# A5000_8MB_MEMCs.net
KiCad netlist of a schematic drawn in Altium Designer
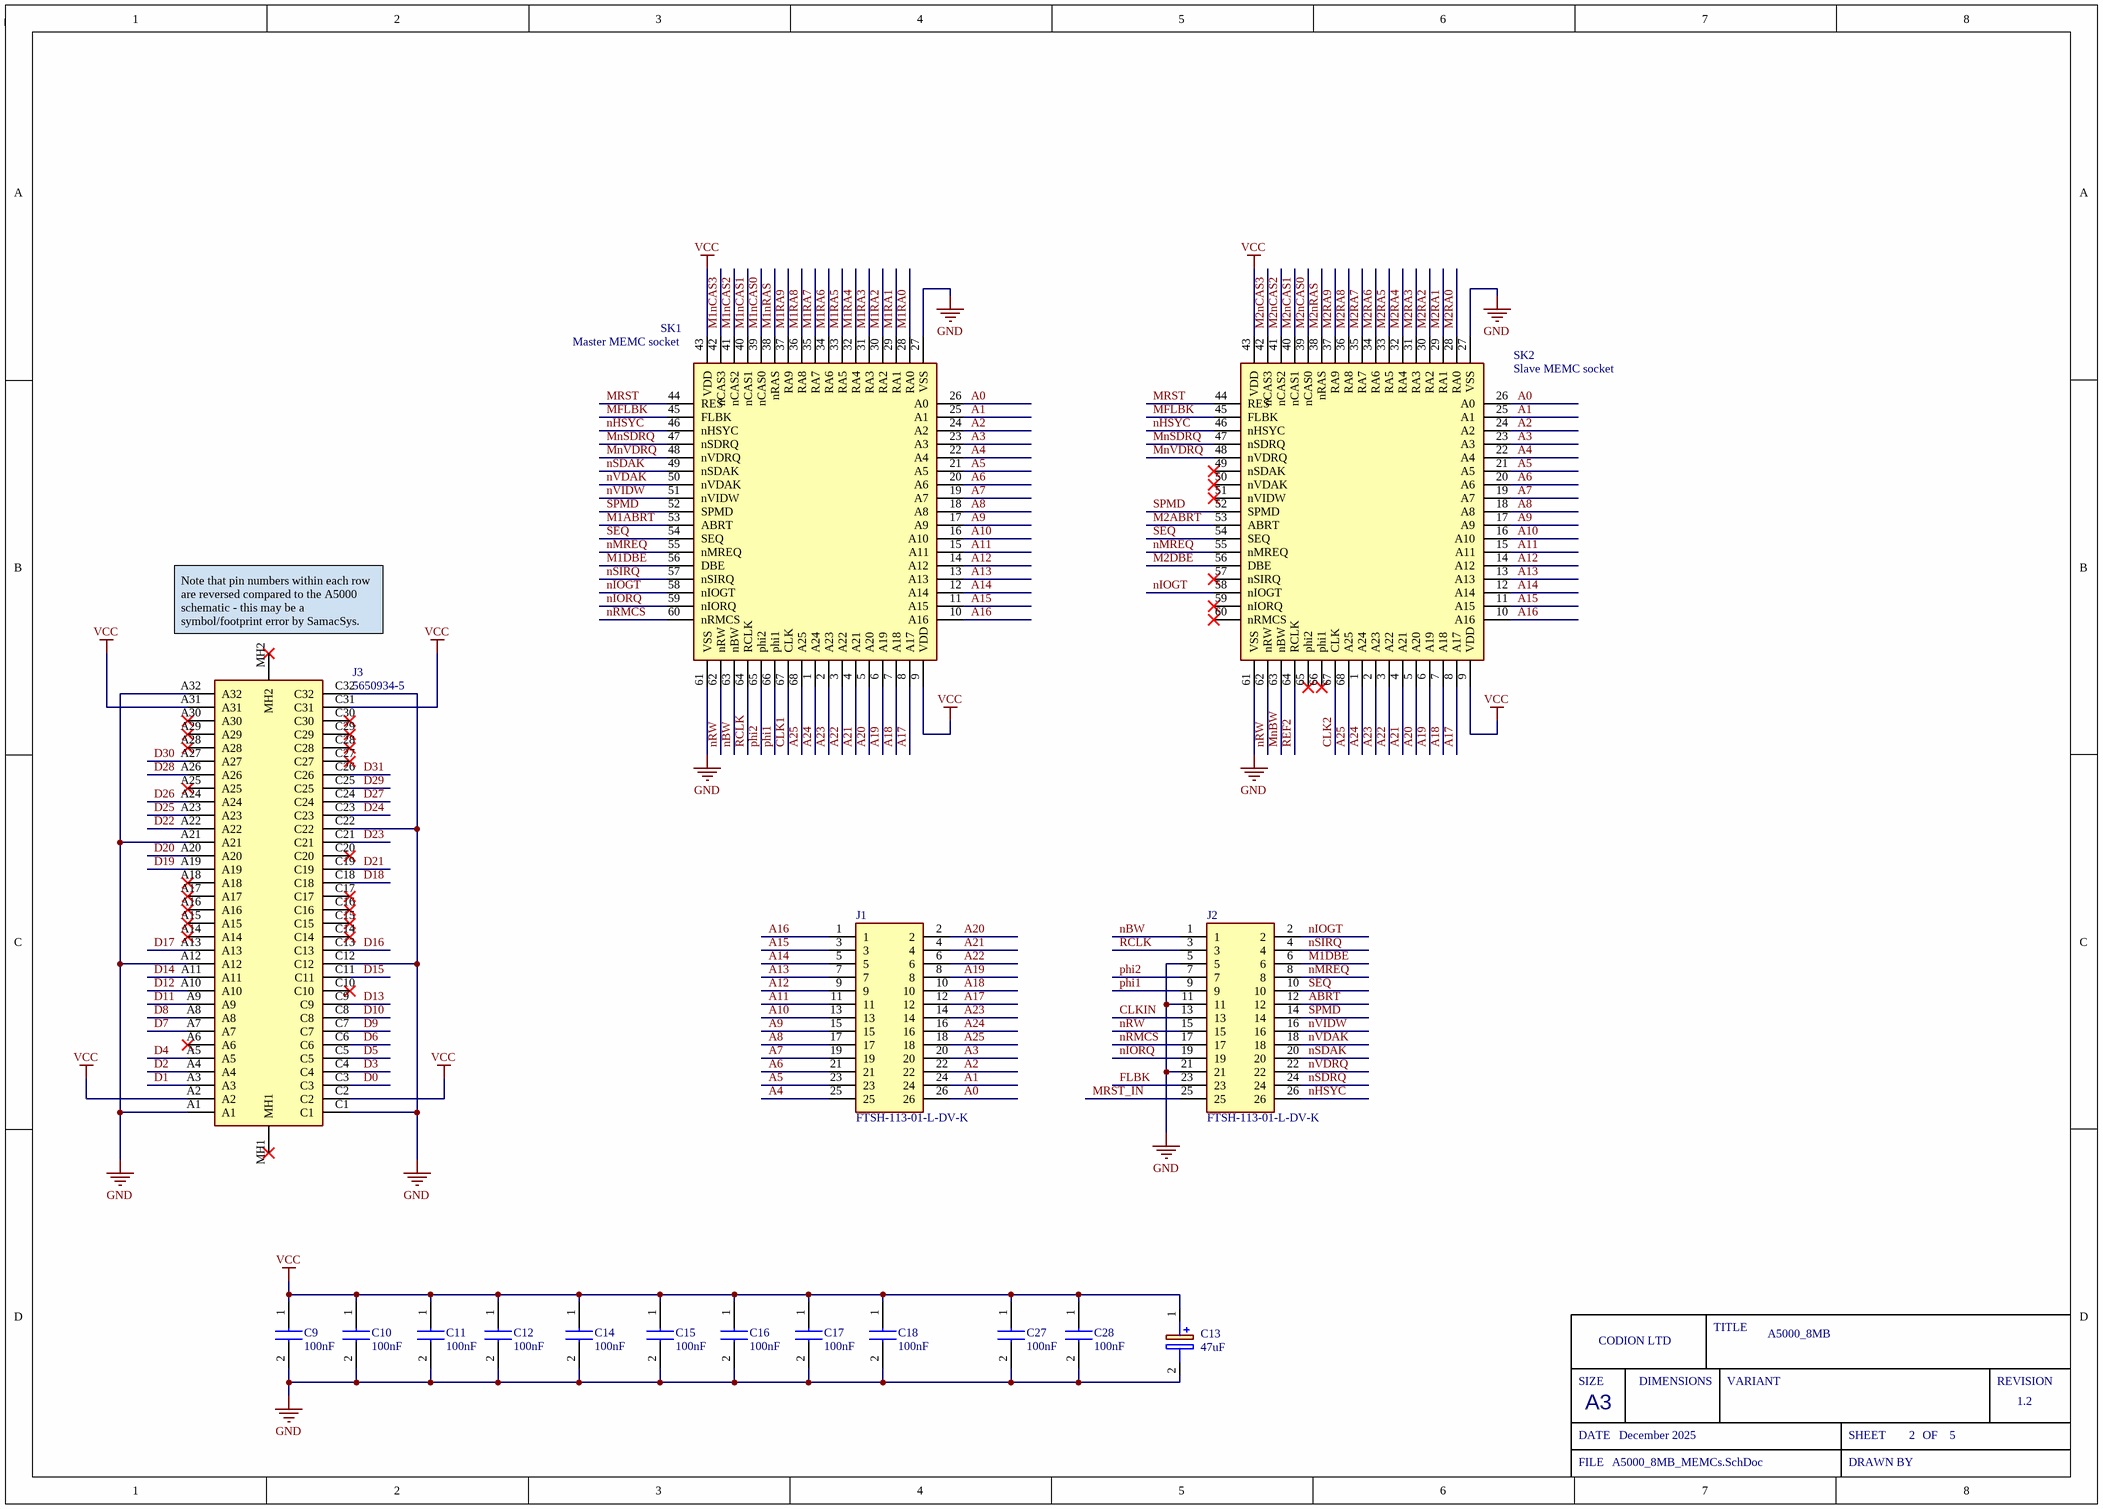
[diagram p0: A5000_8MB_MEMCs.SchDoc]

(export (version "E")
  (design (tool "Eeschema 10.0.6"))
  (components
    (comp (ref "C9")
      (value "100nF")
      (footprint "0805cap")
      (description "Capacitor")
      (fields
        (field (name "MANUFACTURER_PART_NUMBER") "C2012X7R1H104K125AM")
        (field (name "MOUSER PART NUMBER") "810-C2012X7R1H104KT5")
      )
      (libsource (lib "Acorn") (part "100nF0805"))
    )
    (comp (ref "C10")
      (value "100nF")
      (footprint "0805cap")
      (description "Capacitor")
      (fields
        (field (name "MANUFACTURER_PART_NUMBER") "C2012X7R1H104K125AM")
        (field (name "MOUSER PART NUMBER") "810-C2012X7R1H104KT5")
      )
      (libsource (lib "Acorn") (part "100nF0805"))
    )
    (comp (ref "C11")
      (value "100nF")
      (footprint "0805cap")
      (description "Capacitor")
      (fields
        (field (name "MANUFACTURER_PART_NUMBER") "C2012X7R1H104K125AM")
        (field (name "MOUSER PART NUMBER") "810-C2012X7R1H104KT5")
      )
      (libsource (lib "Acorn") (part "100nF0805"))
    )
    (comp (ref "C12")
      (value "100nF")
      (footprint "0805cap")
      (description "Capacitor")
      (fields
        (field (name "MANUFACTURER_PART_NUMBER") "C2012X7R1H104K125AM")
        (field (name "MOUSER PART NUMBER") "810-C2012X7R1H104KT5")
      )
      (libsource (lib "Acorn") (part "100nF0805"))
    )
    (comp (ref "C13")
      (value "47uF")
      (footprint "SamacSys:EEE1AA101SP")
      (description "Capacitor Polarised")
      (fields (field (name "MANUFACTURER_PART_NUMBER") "EEE1VA470WP"))
      (libsource (lib "*") (part "EEE1VA470WP"))
    )
    (comp (ref "C14")
      (value "100nF")
      (footprint "0805cap")
      (description "Capacitor")
      (fields
        (field (name "MANUFACTURER_PART_NUMBER") "C2012X7R1H104K125AM")
        (field (name "MOUSER PART NUMBER") "810-C2012X7R1H104KT5")
      )
      (libsource (lib "Acorn") (part "100nF0805"))
    )
    (comp (ref "C15")
      (value "100nF")
      (footprint "0805cap")
      (description "Capacitor")
      (fields
        (field (name "MANUFACTURER_PART_NUMBER") "C2012X7R1H104K125AM")
        (field (name "MOUSER PART NUMBER") "810-C2012X7R1H104KT5")
      )
      (libsource (lib "Acorn") (part "100nF0805"))
    )
    (comp (ref "C16")
      (value "100nF")
      (footprint "0805cap")
      (description "Capacitor")
      (fields
        (field (name "MANUFACTURER_PART_NUMBER") "C2012X7R1H104K125AM")
        (field (name "MOUSER PART NUMBER") "810-C2012X7R1H104KT5")
      )
      (libsource (lib "Acorn") (part "100nF0805"))
    )
    (comp (ref "C17")
      (value "100nF")
      (footprint "0805cap")
      (description "Capacitor")
      (fields
        (field (name "MANUFACTURER_PART_NUMBER") "C2012X7R1H104K125AM")
        (field (name "MOUSER PART NUMBER") "810-C2012X7R1H104KT5")
      )
      (libsource (lib "Acorn") (part "100nF0805"))
    )
    (comp (ref "C18")
      (value "100nF")
      (footprint "0805cap")
      (description "Capacitor")
      (fields
        (field (name "MANUFACTURER_PART_NUMBER") "C2012X7R1H104K125AM")
        (field (name "MOUSER PART NUMBER") "810-C2012X7R1H104KT5")
      )
      (libsource (lib "Acorn") (part "100nF0805"))
    )
    (comp (ref "C27")
      (value "100nF")
      (footprint "0805cap")
      (description "Capacitor")
      (fields
        (field (name "MANUFACTURER_PART_NUMBER") "C2012X7R1H104K125AM")
        (field (name "MOUSER PART NUMBER") "810-C2012X7R1H104KT5")
      )
      (libsource (lib "Acorn") (part "100nF0805"))
    )
    (comp (ref "C28")
      (value "100nF")
      (footprint "0805cap")
      (description "Capacitor")
      (fields
        (field (name "MANUFACTURER_PART_NUMBER") "C2012X7R1H104K125AM")
        (field (name "MOUSER PART NUMBER") "810-C2012X7R1H104KT5")
      )
      (libsource (lib "Acorn") (part "100nF0805"))
    )
    (comp (ref "J1")
      (value "FTSH-113-01-L-DV-K")
      (footprint "SamacSys:FTSH-113-XX-YYY-DV-K")
      (description "Connector")
      (fields (field (name "MOUSER PART NUMBER") "200-FTSH11301LDVK"))
      (libsource (lib "*") (part "FTSH-113-01-L-DV-K"))
    )
    (comp (ref "J2")
      (value "FTSH-113-01-L-DV-K")
      (footprint "SamacSys:FTSH-113-XX-YYY-DV-K")
      (description "Connector")
      (fields (field (name "MOUSER PART NUMBER") "200-FTSH11301LDVK"))
      (libsource (lib "*") (part "FTSH-113-01-L-DV-K"))
    )
    (comp (ref "J3")
      (value "5650934-5")
      (footprint "SamacSys:56509345")
      (description "Connector")
      (fields (field (name "MOUSER PART NUMBER") "571-5650934-5"))
      (libsource (lib "*") (part "5650934-5"))
    )
    (comp (ref "SK1")
      (value "Master MEMC socket")
      (footprint "MEMC_Socket")
      (description "MEMC socket")
      (fields
        (field (name "MANUFACTURER_PART_NUMBER") "8468-21B1-RK-TR")
        (field (name "MOUSER PART NUMBER") "517-8468-21B1-RK-TR")
      )
      (libsource (lib "Acorn") (part "MEMC_Skt"))
    )
    (comp (ref "SK2")
      (value "Slave MEMC socket")
      (footprint "MEMC_Socket")
      (description "MEMC socket")
      (fields
        (field (name "MANUFACTURER_PART_NUMBER") "8468-21B1-RK-TR")
        (field (name "MOUSER PART NUMBER") "517-8468-21B1-RK-TR")
      )
      (libsource (lib "Acorn") (part "MEMC_Skt"))
    )
  )
  (nets
    (net (code "1") (name "/A0") (class "Default")
      (node (ref "J1") (pin "26") (pinfunction "26_26") (pintype "passive"))
      (node (ref "SK1") (pin "26") (pinfunction "A0_26") (pintype "passive"))
      (node (ref "SK2") (pin "26") (pinfunction "A0_26") (pintype "passive"))
    )
    (net (code "2") (name "/A1") (class "Default")
      (node (ref "J1") (pin "24") (pinfunction "24_24") (pintype "passive"))
      (node (ref "SK1") (pin "25") (pinfunction "A1_25") (pintype "passive"))
      (node (ref "SK2") (pin "25") (pinfunction "A1_25") (pintype "passive"))
    )
    (net (code "3") (name "/A2") (class "Default")
      (node (ref "J1") (pin "22") (pinfunction "22_22") (pintype "passive"))
      (node (ref "SK1") (pin "24") (pinfunction "A2_24") (pintype "passive"))
      (node (ref "SK2") (pin "24") (pinfunction "A2_24") (pintype "passive"))
    )
    (net (code "4") (name "/A3") (class "Default")
      (node (ref "J1") (pin "20") (pinfunction "20_20") (pintype "passive"))
      (node (ref "SK1") (pin "23") (pinfunction "A3_23") (pintype "passive"))
      (node (ref "SK2") (pin "23") (pinfunction "A3_23") (pintype "passive"))
    )
    (net (code "5") (name "/A4") (class "Default")
      (node (ref "J1") (pin "25") (pinfunction "25_25") (pintype "passive"))
      (node (ref "SK1") (pin "22") (pinfunction "A4_22") (pintype "passive"))
      (node (ref "SK2") (pin "22") (pinfunction "A4_22") (pintype "passive"))
    )
    (net (code "6") (name "/A5") (class "Default")
      (node (ref "J1") (pin "23") (pinfunction "23_23") (pintype "passive"))
      (node (ref "SK1") (pin "21") (pinfunction "A5_21") (pintype "passive"))
      (node (ref "SK2") (pin "21") (pinfunction "A5_21") (pintype "passive"))
    )
    (net (code "7") (name "/A6") (class "Default")
      (node (ref "J1") (pin "21") (pinfunction "21_21") (pintype "passive"))
      (node (ref "SK1") (pin "20") (pinfunction "A6_20") (pintype "passive"))
      (node (ref "SK2") (pin "20") (pinfunction "A6_20") (pintype "passive"))
    )
    (net (code "8") (name "/A7") (class "Default")
      (node (ref "J1") (pin "19") (pinfunction "19_19") (pintype "passive"))
      (node (ref "SK1") (pin "19") (pinfunction "A7_19") (pintype "passive"))
      (node (ref "SK2") (pin "19") (pinfunction "A7_19") (pintype "passive"))
    )
    (net (code "9") (name "/A8") (class "Default")
      (node (ref "J1") (pin "17") (pinfunction "17_17") (pintype "passive"))
      (node (ref "SK1") (pin "18") (pinfunction "A8_18") (pintype "passive"))
      (node (ref "SK2") (pin "18") (pinfunction "A8_18") (pintype "passive"))
    )
    (net (code "10") (name "/A9") (class "Default")
      (node (ref "J1") (pin "15") (pinfunction "15_15") (pintype "passive"))
      (node (ref "SK1") (pin "17") (pinfunction "A9_17") (pintype "passive"))
      (node (ref "SK2") (pin "17") (pinfunction "A9_17") (pintype "passive"))
    )
    (net (code "11") (name "/A10") (class "Default")
      (node (ref "J1") (pin "13") (pinfunction "13_13") (pintype "passive"))
      (node (ref "SK1") (pin "16") (pinfunction "A10_16") (pintype "passive"))
      (node (ref "SK2") (pin "16") (pinfunction "A10_16") (pintype "passive"))
    )
    (net (code "12") (name "/A11") (class "Default")
      (node (ref "J1") (pin "11") (pinfunction "11_11") (pintype "passive"))
      (node (ref "SK1") (pin "15") (pinfunction "A11_15") (pintype "passive"))
      (node (ref "SK2") (pin "15") (pinfunction "A11_15") (pintype "passive"))
    )
    (net (code "13") (name "/A12") (class "Default")
      (node (ref "J1") (pin "9") (pinfunction "9_9") (pintype "passive"))
      (node (ref "SK1") (pin "14") (pinfunction "A12_14") (pintype "passive"))
      (node (ref "SK2") (pin "14") (pinfunction "A12_14") (pintype "passive"))
    )
    (net (code "14") (name "/A13") (class "Default")
      (node (ref "J1") (pin "7") (pinfunction "7_7") (pintype "passive"))
      (node (ref "SK1") (pin "13") (pinfunction "A13_13") (pintype "passive"))
      (node (ref "SK2") (pin "13") (pinfunction "A13_13") (pintype "passive"))
    )
    (net (code "15") (name "/A14") (class "Default")
      (node (ref "J1") (pin "5") (pinfunction "5_5") (pintype "passive"))
      (node (ref "SK1") (pin "12") (pinfunction "A14_12") (pintype "passive"))
      (node (ref "SK2") (pin "12") (pinfunction "A14_12") (pintype "passive"))
    )
    (net (code "16") (name "/A15") (class "Default")
      (node (ref "J1") (pin "3") (pinfunction "3_3") (pintype "passive"))
      (node (ref "SK1") (pin "11") (pinfunction "A15_11") (pintype "passive"))
      (node (ref "SK2") (pin "11") (pinfunction "A15_11") (pintype "passive"))
    )
    (net (code "17") (name "/A16") (class "Default")
      (node (ref "J1") (pin "1") (pinfunction "1_1") (pintype "passive"))
      (node (ref "SK1") (pin "10") (pinfunction "A16_10") (pintype "passive"))
      (node (ref "SK2") (pin "10") (pinfunction "A16_10") (pintype "passive"))
    )
    (net (code "18") (name "/A17") (class "Default")
      (node (ref "J1") (pin "12") (pinfunction "12_12") (pintype "passive"))
      (node (ref "SK1") (pin "8") (pinfunction "A17_8") (pintype "passive"))
      (node (ref "SK2") (pin "8") (pinfunction "A17_8") (pintype "passive"))
    )
    (net (code "19") (name "/A18") (class "Default")
      (node (ref "J1") (pin "10") (pinfunction "10_10") (pintype "passive"))
      (node (ref "SK1") (pin "7") (pinfunction "A18_7") (pintype "passive"))
      (node (ref "SK2") (pin "7") (pinfunction "A18_7") (pintype "passive"))
    )
    (net (code "20") (name "/A19") (class "Default")
      (node (ref "J1") (pin "8") (pinfunction "8_8") (pintype "passive"))
      (node (ref "SK1") (pin "6") (pinfunction "A19_6") (pintype "passive"))
      (node (ref "SK2") (pin "6") (pinfunction "A19_6") (pintype "passive"))
    )
    (net (code "21") (name "/A20") (class "Default")
      (node (ref "J1") (pin "2") (pinfunction "2_2") (pintype "passive"))
      (node (ref "SK1") (pin "5") (pinfunction "A20_5") (pintype "passive"))
      (node (ref "SK2") (pin "5") (pinfunction "A20_5") (pintype "passive"))
    )
    (net (code "22") (name "/A21") (class "Default")
      (node (ref "J1") (pin "4") (pinfunction "4_4") (pintype "passive"))
      (node (ref "SK1") (pin "4") (pinfunction "A21_4") (pintype "passive"))
      (node (ref "SK2") (pin "4") (pinfunction "A21_4") (pintype "passive"))
    )
    (net (code "23") (name "/A22") (class "Default")
      (node (ref "J1") (pin "6") (pinfunction "6_6") (pintype "passive"))
      (node (ref "SK1") (pin "3") (pinfunction "A22_3") (pintype "passive"))
      (node (ref "SK2") (pin "3") (pinfunction "A22_3") (pintype "passive"))
    )
    (net (code "24") (name "/A23") (class "Default")
      (node (ref "J1") (pin "14") (pinfunction "14_14") (pintype "passive"))
      (node (ref "SK1") (pin "2") (pinfunction "A23_2") (pintype "passive"))
      (node (ref "SK2") (pin "2") (pinfunction "A23_2") (pintype "passive"))
    )
    (net (code "25") (name "/A24") (class "Default")
      (node (ref "J1") (pin "16") (pinfunction "16_16") (pintype "passive"))
      (node (ref "SK1") (pin "1") (pinfunction "A24_1") (pintype "passive"))
      (node (ref "SK2") (pin "1") (pinfunction "A24_1") (pintype "passive"))
    )
    (net (code "26") (name "/A25") (class "Default")
      (node (ref "J1") (pin "18") (pinfunction "18_18") (pintype "passive"))
      (node (ref "SK1") (pin "68") (pinfunction "A25_68") (pintype "passive"))
      (node (ref "SK2") (pin "68") (pinfunction "A25_68") (pintype "passive"))
    )
    (net (code "27") (name "/ABRT") (class "Default")
      (node (ref "J2") (pin "12") (pinfunction "12_12") (pintype "passive"))
    )
    (net (code "28") (name "/CLK1") (class "Default")
      (node (ref "SK1") (pin "67") (pinfunction "CLK_67") (pintype "passive"))
    )
    (net (code "29") (name "/CLK2") (class "Default")
      (node (ref "SK2") (pin "67") (pinfunction "CLK_67") (pintype "passive"))
    )
    (net (code "30") (name "/CLKIN") (class "Default")
      (node (ref "J2") (pin "13") (pinfunction "13_13") (pintype "passive"))
    )
    (net (code "31") (name "/D0") (class "Default")
      (node (ref "J3") (pin "C3") (pinfunction "C3_C3") (pintype "passive"))
    )
    (net (code "32") (name "/D1") (class "Default")
      (node (ref "J3") (pin "A3") (pinfunction "A3_A3") (pintype "passive"))
    )
    (net (code "33") (name "/D2") (class "Default")
      (node (ref "J3") (pin "A4") (pinfunction "A4_A4") (pintype "passive"))
    )
    (net (code "34") (name "/D3") (class "Default")
      (node (ref "J3") (pin "C4") (pinfunction "C4_C4") (pintype "passive"))
    )
    (net (code "35") (name "/D4") (class "Default")
      (node (ref "J3") (pin "A5") (pinfunction "A5_A5") (pintype "passive"))
    )
    (net (code "36") (name "/D5") (class "Default")
      (node (ref "J3") (pin "C5") (pinfunction "C5_C5") (pintype "passive"))
    )
    (net (code "37") (name "/D6") (class "Default")
      (node (ref "J3") (pin "C6") (pinfunction "C6_C6") (pintype "passive"))
    )
    (net (code "38") (name "/D7") (class "Default")
      (node (ref "J3") (pin "A7") (pinfunction "A7_A7") (pintype "passive"))
    )
    (net (code "39") (name "/D8") (class "Default")
      (node (ref "J3") (pin "A8") (pinfunction "A8_A8") (pintype "passive"))
    )
    (net (code "40") (name "/D9") (class "Default")
      (node (ref "J3") (pin "C7") (pinfunction "C7_C7") (pintype "passive"))
    )
    (net (code "41") (name "/D10") (class "Default")
      (node (ref "J3") (pin "C8") (pinfunction "C8_C8") (pintype "passive"))
    )
    (net (code "42") (name "/D11") (class "Default")
      (node (ref "J3") (pin "A9") (pinfunction "A9_A9") (pintype "passive"))
    )
    (net (code "43") (name "/D12") (class "Default")
      (node (ref "J3") (pin "A10") (pinfunction "A10_A10") (pintype "passive"))
    )
    (net (code "44") (name "/D13") (class "Default")
      (node (ref "J3") (pin "C9") (pinfunction "C9_C9") (pintype "passive"))
    )
    (net (code "45") (name "/D14") (class "Default")
      (node (ref "J3") (pin "A11") (pinfunction "A11_A11") (pintype "passive"))
    )
    (net (code "46") (name "/D15") (class "Default")
      (node (ref "J3") (pin "C11") (pinfunction "C11_C11") (pintype "passive"))
    )
    (net (code "47") (name "/D16") (class "Default")
      (node (ref "J3") (pin "C13") (pinfunction "C13_C13") (pintype "passive"))
    )
    (net (code "48") (name "/D17") (class "Default")
      (node (ref "J3") (pin "A13") (pinfunction "A13_A13") (pintype "passive"))
    )
    (net (code "49") (name "/D18") (class "Default")
      (node (ref "J3") (pin "C18") (pinfunction "C18_C18") (pintype "passive"))
    )
    (net (code "50") (name "/D19") (class "Default")
      (node (ref "J3") (pin "A19") (pinfunction "A19_A19") (pintype "passive"))
    )
    (net (code "51") (name "/D20") (class "Default")
      (node (ref "J3") (pin "A20") (pinfunction "A20_A20") (pintype "passive"))
    )
    (net (code "52") (name "/D21") (class "Default")
      (node (ref "J3") (pin "C19") (pinfunction "C19_C19") (pintype "passive"))
    )
    (net (code "53") (name "/D22") (class "Default")
      (node (ref "J3") (pin "A22") (pinfunction "A22_A22") (pintype "passive"))
    )
    (net (code "54") (name "/D23") (class "Default")
      (node (ref "J3") (pin "C21") (pinfunction "C21_C21") (pintype "passive"))
    )
    (net (code "55") (name "/D24") (class "Default")
      (node (ref "J3") (pin "C23") (pinfunction "C23_C23") (pintype "passive"))
    )
    (net (code "56") (name "/D25") (class "Default")
      (node (ref "J3") (pin "A23") (pinfunction "A23_A23") (pintype "passive"))
    )
    (net (code "57") (name "/D26") (class "Default")
      (node (ref "J3") (pin "A24") (pinfunction "A24_A24") (pintype "passive"))
    )
    (net (code "58") (name "/D27") (class "Default")
      (node (ref "J3") (pin "C24") (pinfunction "C24_C24") (pintype "passive"))
    )
    (net (code "59") (name "/D28") (class "Default")
      (node (ref "J3") (pin "A26") (pinfunction "A26_A26") (pintype "passive"))
    )
    (net (code "60") (name "/D29") (class "Default")
      (node (ref "J3") (pin "C25") (pinfunction "C25_C25") (pintype "passive"))
    )
    (net (code "61") (name "/D30") (class "Default")
      (node (ref "J3") (pin "A27") (pinfunction "A27_A27") (pintype "passive"))
    )
    (net (code "62") (name "/D31") (class "Default")
      (node (ref "J3") (pin "C26") (pinfunction "C26_C26") (pintype "passive"))
    )
    (net (code "63") (name "/FLBK") (class "Default")
      (node (ref "J2") (pin "23") (pinfunction "23_23") (pintype "passive"))
    )
    (net (code "64") (name "/M1ABRT") (class "Default")
      (node (ref "SK1") (pin "53") (pinfunction "ABRT_53") (pintype "passive"))
    )
    (net (code "65") (name "/M1DBE") (class "Default")
      (node (ref "J2") (pin "6") (pinfunction "6_6") (pintype "passive"))
      (node (ref "SK1") (pin "56") (pinfunction "DBE_56") (pintype "passive"))
    )
    (net (code "66") (name "/M1RA0") (class "Default")
      (node (ref "SK1") (pin "28") (pinfunction "RA0_28") (pintype "passive"))
    )
    (net (code "67") (name "/M1RA1") (class "Default")
      (node (ref "SK1") (pin "29") (pinfunction "RA1_29") (pintype "passive"))
    )
    (net (code "68") (name "/M1RA2") (class "Default")
      (node (ref "SK1") (pin "30") (pinfunction "RA2_30") (pintype "passive"))
    )
    (net (code "69") (name "/M1RA3") (class "Default")
      (node (ref "SK1") (pin "31") (pinfunction "RA3_31") (pintype "passive"))
    )
    (net (code "70") (name "/M1RA4") (class "Default")
      (node (ref "SK1") (pin "32") (pinfunction "RA4_32") (pintype "passive"))
    )
    (net (code "71") (name "/M1RA5") (class "Default")
      (node (ref "SK1") (pin "33") (pinfunction "RA5_33") (pintype "passive"))
    )
    (net (code "72") (name "/M1RA6") (class "Default")
      (node (ref "SK1") (pin "34") (pinfunction "RA6_34") (pintype "passive"))
    )
    (net (code "73") (name "/M1RA7") (class "Default")
      (node (ref "SK1") (pin "35") (pinfunction "RA7_35") (pintype "passive"))
    )
    (net (code "74") (name "/M1RA8") (class "Default")
      (node (ref "SK1") (pin "36") (pinfunction "RA8_36") (pintype "passive"))
    )
    (net (code "75") (name "/M1RA9") (class "Default")
      (node (ref "SK1") (pin "37") (pinfunction "RA9_37") (pintype "passive"))
    )
    (net (code "76") (name "/M1nCAS0") (class "Default")
      (node (ref "SK1") (pin "39") (pinfunction "nCAS0_39") (pintype "passive"))
    )
    (net (code "77") (name "/M1nCAS1") (class "Default")
      (node (ref "SK1") (pin "40") (pinfunction "nCAS1_40") (pintype "passive"))
    )
    (net (code "78") (name "/M1nCAS2") (class "Default")
      (node (ref "SK1") (pin "41") (pinfunction "nCAS2_41") (pintype "passive"))
    )
    (net (code "79") (name "/M1nCAS3") (class "Default")
      (node (ref "SK1") (pin "42") (pinfunction "nCAS3_42") (pintype "passive"))
    )
    (net (code "80") (name "/M1nRAS") (class "Default")
      (node (ref "SK1") (pin "38") (pinfunction "nRAS_38") (pintype "passive"))
    )
    (net (code "81") (name "/M2ABRT") (class "Default")
      (node (ref "SK2") (pin "53") (pinfunction "ABRT_53") (pintype "passive"))
    )
    (net (code "82") (name "/M2DBE") (class "Default")
      (node (ref "SK2") (pin "56") (pinfunction "DBE_56") (pintype "passive"))
    )
    (net (code "83") (name "/M2RA0") (class "Default")
      (node (ref "SK2") (pin "28") (pinfunction "RA0_28") (pintype "passive"))
    )
    (net (code "84") (name "/M2RA1") (class "Default")
      (node (ref "SK2") (pin "29") (pinfunction "RA1_29") (pintype "passive"))
    )
    (net (code "85") (name "/M2RA2") (class "Default")
      (node (ref "SK2") (pin "30") (pinfunction "RA2_30") (pintype "passive"))
    )
    (net (code "86") (name "/M2RA3") (class "Default")
      (node (ref "SK2") (pin "31") (pinfunction "RA3_31") (pintype "passive"))
    )
    (net (code "87") (name "/M2RA4") (class "Default")
      (node (ref "SK2") (pin "32") (pinfunction "RA4_32") (pintype "passive"))
    )
    (net (code "88") (name "/M2RA5") (class "Default")
      (node (ref "SK2") (pin "33") (pinfunction "RA5_33") (pintype "passive"))
    )
    (net (code "89") (name "/M2RA6") (class "Default")
      (node (ref "SK2") (pin "34") (pinfunction "RA6_34") (pintype "passive"))
    )
    (net (code "90") (name "/M2RA7") (class "Default")
      (node (ref "SK2") (pin "35") (pinfunction "RA7_35") (pintype "passive"))
    )
    (net (code "91") (name "/M2RA8") (class "Default")
      (node (ref "SK2") (pin "36") (pinfunction "RA8_36") (pintype "passive"))
    )
    (net (code "92") (name "/M2RA9") (class "Default")
      (node (ref "SK2") (pin "37") (pinfunction "RA9_37") (pintype "passive"))
    )
    (net (code "93") (name "/M2nCAS0") (class "Default")
      (node (ref "SK2") (pin "39") (pinfunction "nCAS0_39") (pintype "passive"))
    )
    (net (code "94") (name "/M2nCAS1") (class "Default")
      (node (ref "SK2") (pin "40") (pinfunction "nCAS1_40") (pintype "passive"))
    )
    (net (code "95") (name "/M2nCAS2") (class "Default")
      (node (ref "SK2") (pin "41") (pinfunction "nCAS2_41") (pintype "passive"))
    )
    (net (code "96") (name "/M2nCAS3") (class "Default")
      (node (ref "SK2") (pin "42") (pinfunction "nCAS3_42") (pintype "passive"))
    )
    (net (code "97") (name "/M2nRAS") (class "Default")
      (node (ref "SK2") (pin "38") (pinfunction "nRAS_38") (pintype "passive"))
    )
    (net (code "98") (name "/MFLBK") (class "Default")
      (node (ref "SK1") (pin "45") (pinfunction "FLBK_45") (pintype "passive"))
      (node (ref "SK2") (pin "45") (pinfunction "FLBK_45") (pintype "passive"))
    )
    (net (code "99") (name "/MRST") (class "Default")
      (node (ref "SK1") (pin "44") (pinfunction "RES_44") (pintype "passive"))
      (node (ref "SK2") (pin "44") (pinfunction "RES_44") (pintype "passive"))
    )
    (net (code "100") (name "/MRST_IN") (class "Default")
      (node (ref "J2") (pin "25") (pinfunction "25_25") (pintype "passive"))
    )
    (net (code "101") (name "/MnBW") (class "Default")
      (node (ref "SK2") (pin "63") (pinfunction "nBW_63") (pintype "passive"))
    )
    (net (code "102") (name "/MnSDRQ") (class "Default")
      (node (ref "SK1") (pin "47") (pinfunction "nSDRQ_47") (pintype "passive"))
      (node (ref "SK2") (pin "47") (pinfunction "nSDRQ_47") (pintype "passive"))
    )
    (net (code "103") (name "/MnVDRQ") (class "Default")
      (node (ref "SK1") (pin "48") (pinfunction "nVDRQ_48") (pintype "passive"))
      (node (ref "SK2") (pin "48") (pinfunction "nVDRQ_48") (pintype "passive"))
    )
    (net (code "104") (name "/RCLK") (class "Default")
      (node (ref "J2") (pin "3") (pinfunction "3_3") (pintype "passive"))
      (node (ref "SK1") (pin "64") (pinfunction "RCLK_64") (pintype "passive"))
    )
    (net (code "105") (name "/REF2") (class "Default")
      (node (ref "SK2") (pin "64") (pinfunction "RCLK_64") (pintype "passive"))
    )
    (net (code "106") (name "/SEQ") (class "Default")
      (node (ref "J2") (pin "10") (pinfunction "10_10") (pintype "passive"))
      (node (ref "SK1") (pin "54") (pinfunction "SEQ_54") (pintype "passive"))
      (node (ref "SK2") (pin "54") (pinfunction "SEQ_54") (pintype "passive"))
    )
    (net (code "107") (name "/SPMD") (class "Default")
      (node (ref "J2") (pin "14") (pinfunction "14_14") (pintype "passive"))
      (node (ref "SK1") (pin "52") (pinfunction "SPMD_52") (pintype "passive"))
      (node (ref "SK2") (pin "52") (pinfunction "SPMD_52") (pintype "passive"))
    )
    (net (code "108") (name "/nBW") (class "Default")
      (node (ref "J2") (pin "1") (pinfunction "1_1") (pintype "passive"))
      (node (ref "SK1") (pin "63") (pinfunction "nBW_63") (pintype "passive"))
    )
    (net (code "109") (name "/nHSYC") (class "Default")
      (node (ref "J2") (pin "26") (pinfunction "26_26") (pintype "passive"))
      (node (ref "SK1") (pin "46") (pinfunction "nHSYC_46") (pintype "passive"))
      (node (ref "SK2") (pin "46") (pinfunction "nHSYC_46") (pintype "passive"))
    )
    (net (code "110") (name "/nIOGT") (class "Default")
      (node (ref "J2") (pin "2") (pinfunction "2_2") (pintype "passive"))
      (node (ref "SK1") (pin "58") (pinfunction "nIOGT_58") (pintype "passive"))
      (node (ref "SK2") (pin "58") (pinfunction "nIOGT_58") (pintype "passive"))
    )
    (net (code "111") (name "/nIORQ") (class "Default")
      (node (ref "J2") (pin "19") (pinfunction "19_19") (pintype "passive"))
      (node (ref "SK1") (pin "59") (pinfunction "nIORQ_59") (pintype "passive"))
    )
    (net (code "112") (name "/nMREQ") (class "Default")
      (node (ref "J2") (pin "8") (pinfunction "8_8") (pintype "passive"))
      (node (ref "SK1") (pin "55") (pinfunction "nMREQ_55") (pintype "passive"))
      (node (ref "SK2") (pin "55") (pinfunction "nMREQ_55") (pintype "passive"))
    )
    (net (code "113") (name "/nRMCS") (class "Default")
      (node (ref "J2") (pin "17") (pinfunction "17_17") (pintype "passive"))
      (node (ref "SK1") (pin "60") (pinfunction "nRMCS_60") (pintype "passive"))
    )
    (net (code "114") (name "/nRW") (class "Default")
      (node (ref "J2") (pin "15") (pinfunction "15_15") (pintype "passive"))
      (node (ref "SK1") (pin "62") (pinfunction "nRW_62") (pintype "passive"))
      (node (ref "SK2") (pin "62") (pinfunction "nRW_62") (pintype "passive"))
    )
    (net (code "115") (name "/nSDAK") (class "Default")
      (node (ref "J2") (pin "20") (pinfunction "20_20") (pintype "passive"))
      (node (ref "SK1") (pin "49") (pinfunction "nSDAK_49") (pintype "passive"))
    )
    (net (code "116") (name "/nSDRQ") (class "Default")
      (node (ref "J2") (pin "24") (pinfunction "24_24") (pintype "passive"))
    )
    (net (code "117") (name "/nSIRQ") (class "Default")
      (node (ref "J2") (pin "4") (pinfunction "4_4") (pintype "passive"))
      (node (ref "SK1") (pin "57") (pinfunction "nSIRQ_57") (pintype "passive"))
    )
    (net (code "118") (name "/nVDAK") (class "Default")
      (node (ref "J2") (pin "18") (pinfunction "18_18") (pintype "passive"))
      (node (ref "SK1") (pin "50") (pinfunction "nVDAK_50") (pintype "passive"))
    )
    (net (code "119") (name "/nVDRQ") (class "Default")
      (node (ref "J2") (pin "22") (pinfunction "22_22") (pintype "passive"))
    )
    (net (code "120") (name "/nVIDW") (class "Default")
      (node (ref "J2") (pin "16") (pinfunction "16_16") (pintype "passive"))
      (node (ref "SK1") (pin "51") (pinfunction "nVIDW_51") (pintype "passive"))
    )
    (net (code "121") (name "/phi1") (class "Default")
      (node (ref "J2") (pin "9") (pinfunction "9_9") (pintype "passive"))
      (node (ref "SK1") (pin "66") (pinfunction "phi1_66") (pintype "passive"))
    )
    (net (code "122") (name "/phi2") (class "Default")
      (node (ref "J2") (pin "7") (pinfunction "7_7") (pintype "passive"))
      (node (ref "SK1") (pin "65") (pinfunction "phi2_65") (pintype "passive"))
    )
    (net (code "123") (name "GND") (class "Default")
      (node (ref "C10") (pin "2") (pinfunction "2_2") (pintype "passive"))
      (node (ref "C11") (pin "2") (pinfunction "2_2") (pintype "passive"))
      (node (ref "C12") (pin "2") (pinfunction "2_2") (pintype "passive"))
      (node (ref "C13") (pin "2") (pinfunction "-_2") (pintype "passive"))
      (node (ref "C14") (pin "2") (pinfunction "2_2") (pintype "passive"))
      (node (ref "C15") (pin "2") (pinfunction "2_2") (pintype "passive"))
      (node (ref "C16") (pin "2") (pinfunction "2_2") (pintype "passive"))
      (node (ref "C17") (pin "2") (pinfunction "2_2") (pintype "passive"))
      (node (ref "C18") (pin "2") (pinfunction "2_2") (pintype "passive"))
      (node (ref "C27") (pin "2") (pinfunction "2_2") (pintype "passive"))
      (node (ref "C28") (pin "2") (pinfunction "2_2") (pintype "passive"))
      (node (ref "C9") (pin "2") (pinfunction "2_2") (pintype "passive"))
      (node (ref "J2") (pin "11") (pinfunction "11_11") (pintype "passive"))
      (node (ref "J2") (pin "21") (pinfunction "21_21") (pintype "passive"))
      (node (ref "J2") (pin "5") (pinfunction "5_5") (pintype "passive"))
      (node (ref "J3") (pin "A1") (pinfunction "A1_A1") (pintype "passive"))
      (node (ref "J3") (pin "A12") (pinfunction "A12_A12") (pintype "passive"))
      (node (ref "J3") (pin "A21") (pinfunction "A21_A21") (pintype "passive"))
      (node (ref "J3") (pin "A32") (pinfunction "A32_A32") (pintype "passive"))
      (node (ref "J3") (pin "C1") (pinfunction "C1_C1") (pintype "passive"))
      (node (ref "J3") (pin "C12") (pinfunction "C12_C12") (pintype "passive"))
      (node (ref "J3") (pin "C22") (pinfunction "C22_C22") (pintype "passive"))
      (node (ref "J3") (pin "C32") (pinfunction "C32_C32") (pintype "passive"))
      (node (ref "SK1") (pin "27") (pinfunction "VSS_27") (pintype "passive"))
      (node (ref "SK1") (pin "61") (pinfunction "VSS_61") (pintype "passive"))
      (node (ref "SK2") (pin "27") (pinfunction "VSS_27") (pintype "passive"))
      (node (ref "SK2") (pin "61") (pinfunction "VSS_61") (pintype "passive"))
    )
    (net (code "124") (name "VCC") (class "Default")
      (node (ref "C10") (pin "1") (pinfunction "1_1") (pintype "passive"))
      (node (ref "C11") (pin "1") (pinfunction "1_1") (pintype "passive"))
      (node (ref "C12") (pin "1") (pinfunction "1_1") (pintype "passive"))
      (node (ref "C13") (pin "1") (pinfunction "+_1") (pintype "passive"))
      (node (ref "C14") (pin "1") (pinfunction "1_1") (pintype "passive"))
      (node (ref "C15") (pin "1") (pinfunction "1_1") (pintype "passive"))
      (node (ref "C16") (pin "1") (pinfunction "1_1") (pintype "passive"))
      (node (ref "C17") (pin "1") (pinfunction "1_1") (pintype "passive"))
      (node (ref "C18") (pin "1") (pinfunction "1_1") (pintype "passive"))
      (node (ref "C27") (pin "1") (pinfunction "1_1") (pintype "passive"))
      (node (ref "C28") (pin "1") (pinfunction "1_1") (pintype "passive"))
      (node (ref "C9") (pin "1") (pinfunction "1_1") (pintype "passive"))
      (node (ref "J3") (pin "A2") (pinfunction "A2_A2") (pintype "passive"))
      (node (ref "J3") (pin "A31") (pinfunction "A31_A31") (pintype "passive"))
      (node (ref "J3") (pin "C2") (pinfunction "C2_C2") (pintype "passive"))
      (node (ref "J3") (pin "C31") (pinfunction "C31_C31") (pintype "passive"))
      (node (ref "SK1") (pin "43") (pinfunction "VDD_43") (pintype "passive"))
      (node (ref "SK1") (pin "9") (pinfunction "VDD_9") (pintype "passive"))
      (node (ref "SK2") (pin "43") (pinfunction "VDD_43") (pintype "passive"))
      (node (ref "SK2") (pin "9") (pinfunction "VDD_9") (pintype "passive"))
    )
    (net (code "125") (name "unconnected-(J3-PadA6)") (class "Default")
      (node (ref "J3") (pin "A6") (pinfunction "A6_A6") (pintype "passive+no_connect"))
    )
    (net (code "126") (name "unconnected-(J3-PadA14)") (class "Default")
      (node (ref "J3") (pin "A14") (pinfunction "A14_A14") (pintype "passive+no_connect"))
    )
    (net (code "127") (name "unconnected-(J3-PadA15)") (class "Default")
      (node (ref "J3") (pin "A15") (pinfunction "A15_A15") (pintype "passive+no_connect"))
    )
    (net (code "128") (name "unconnected-(J3-PadA16)") (class "Default")
      (node (ref "J3") (pin "A16") (pinfunction "A16_A16") (pintype "passive+no_connect"))
    )
    (net (code "129") (name "unconnected-(J3-PadA17)") (class "Default")
      (node (ref "J3") (pin "A17") (pinfunction "A17_A17") (pintype "passive+no_connect"))
    )
    (net (code "130") (name "unconnected-(J3-PadA18)") (class "Default")
      (node (ref "J3") (pin "A18") (pinfunction "A18_A18") (pintype "passive+no_connect"))
    )
    (net (code "131") (name "unconnected-(J3-PadA25)") (class "Default")
      (node (ref "J3") (pin "A25") (pinfunction "A25_A25") (pintype "passive+no_connect"))
    )
    (net (code "132") (name "unconnected-(J3-PadA28)") (class "Default")
      (node (ref "J3") (pin "A28") (pinfunction "A28_A28") (pintype "passive+no_connect"))
    )
    (net (code "133") (name "unconnected-(J3-PadA29)") (class "Default")
      (node (ref "J3") (pin "A29") (pinfunction "A29_A29") (pintype "passive+no_connect"))
    )
    (net (code "134") (name "unconnected-(J3-PadA30)") (class "Default")
      (node (ref "J3") (pin "A30") (pinfunction "A30_A30") (pintype "passive+no_connect"))
    )
    (net (code "135") (name "unconnected-(J3-PadC10)") (class "Default")
      (node (ref "J3") (pin "C10") (pinfunction "C10_C10") (pintype "passive+no_connect"))
    )
    (net (code "136") (name "unconnected-(J3-PadC14)") (class "Default")
      (node (ref "J3") (pin "C14") (pinfunction "C14_C14") (pintype "passive+no_connect"))
    )
    (net (code "137") (name "unconnected-(J3-PadC15)") (class "Default")
      (node (ref "J3") (pin "C15") (pinfunction "C15_C15") (pintype "passive+no_connect"))
    )
    (net (code "138") (name "unconnected-(J3-PadC16)") (class "Default")
      (node (ref "J3") (pin "C16") (pinfunction "C16_C16") (pintype "passive+no_connect"))
    )
    (net (code "139") (name "unconnected-(J3-PadC17)") (class "Default")
      (node (ref "J3") (pin "C17") (pinfunction "C17_C17") (pintype "passive+no_connect"))
    )
    (net (code "140") (name "unconnected-(J3-PadC20)") (class "Default")
      (node (ref "J3") (pin "C20") (pinfunction "C20_C20") (pintype "passive+no_connect"))
    )
    (net (code "141") (name "unconnected-(J3-PadC27)") (class "Default")
      (node (ref "J3") (pin "C27") (pinfunction "C27_C27") (pintype "passive+no_connect"))
    )
    (net (code "142") (name "unconnected-(J3-PadC28)") (class "Default")
      (node (ref "J3") (pin "C28") (pinfunction "C28_C28") (pintype "passive+no_connect"))
    )
    (net (code "143") (name "unconnected-(J3-PadC29)") (class "Default")
      (node (ref "J3") (pin "C29") (pinfunction "C29_C29") (pintype "passive+no_connect"))
    )
    (net (code "144") (name "unconnected-(J3-PadC30)") (class "Default")
      (node (ref "J3") (pin "C30") (pinfunction "C30_C30") (pintype "passive+no_connect"))
    )
    (net (code "145") (name "unconnected-(J3-PadMH1)") (class "Default")
      (node (ref "J3") (pin "MH1") (pinfunction "MH1_MH1") (pintype "passive+no_connect"))
    )
    (net (code "146") (name "unconnected-(J3-PadMH2)") (class "Default")
      (node (ref "J3") (pin "MH2") (pinfunction "MH2_MH2") (pintype "passive+no_connect"))
    )
    (net (code "147") (name "unconnected-(SK2-nIORQ-Pad59)") (class "Default")
      (node (ref "SK2") (pin "59") (pinfunction "nIORQ_59") (pintype "passive+no_connect"))
    )
    (net (code "148") (name "unconnected-(SK2-nRMCS-Pad60)") (class "Default")
      (node (ref "SK2") (pin "60") (pinfunction "nRMCS_60") (pintype "passive+no_connect"))
    )
    (net (code "149") (name "unconnected-(SK2-nSDAK-Pad49)") (class "Default")
      (node (ref "SK2") (pin "49") (pinfunction "nSDAK_49") (pintype "passive+no_connect"))
    )
    (net (code "150") (name "unconnected-(SK2-nSIRQ-Pad57)") (class "Default")
      (node (ref "SK2") (pin "57") (pinfunction "nSIRQ_57") (pintype "passive+no_connect"))
    )
    (net (code "151") (name "unconnected-(SK2-nVDAK-Pad50)") (class "Default")
      (node (ref "SK2") (pin "50") (pinfunction "nVDAK_50") (pintype "passive+no_connect"))
    )
    (net (code "152") (name "unconnected-(SK2-nVIDW-Pad51)") (class "Default")
      (node (ref "SK2") (pin "51") (pinfunction "nVIDW_51") (pintype "passive+no_connect"))
    )
    (net (code "153") (name "unconnected-(SK2-phi1-Pad66)") (class "Default")
      (node (ref "SK2") (pin "66") (pinfunction "phi1_66") (pintype "passive+no_connect"))
    )
    (net (code "154") (name "unconnected-(SK2-phi2-Pad65)") (class "Default")
      (node (ref "SK2") (pin "65") (pinfunction "phi2_65") (pintype "passive+no_connect"))
    )
  )
)
